# CAN_v1.net
KiCad netlist of a schematic drawn in Altium Designer
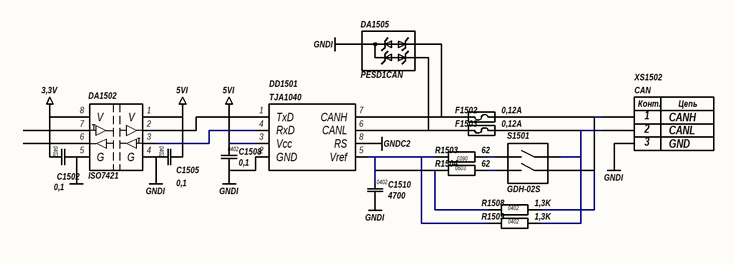
[diagram p0: CAN v1.SchDoc]

(export (version "E")
  (design (tool "Eeschema 10.0.6"))
  (components
    (comp (ref "C1502")
      (value "0,1")
      (footprint "CAP0402")
      (description "Конденсатор чип")
      (libsource (lib "EwgPassive") (part "CAP_0402"))
    )
    (comp (ref "C1505")
      (value "0,1")
      (footprint "CAP0402")
      (description "Конденсатор чип")
      (libsource (lib "EwgPassive") (part "CAP_0402"))
    )
    (comp (ref "C1508")
      (value "0,1")
      (footprint "CAP0402")
      (description "Конденсатор чип")
      (libsource (lib "EwgPassive") (part "CAP_0402"))
    )
    (comp (ref "C1510")
      (value "4700")
      (footprint "CAP0402")
      (description "Конденсатор чип")
      (libsource (lib "EwgPassive") (part "CAP_0402"))
    )
    (comp (ref "DA1502")
      (value "ISO7421")
      (footprint "SO8")
      (description "Цифровой изолятор 1 вх 1 вых")
      (libsource (lib "EwgOpto") (part "ISO7421"))
    )
    (comp (ref "DA1505")
      (value "PESD1CAN")
      (footprint "SOT-23")
      (description "ESD-CAN защита")
      (libsource (lib "EwgActive") (part "PESD1CAN"))
    )
    (comp (ref "DD1501")
      (value "TJA1040")
      (footprint "SO8")
      (description "Драйвер CAN")
      (libsource (lib "EwgMicrochips") (part "TJA1040"))
    )
    (comp (ref "F1502")
      (value "0,12A")
      (footprint "MF-NSMF")
      (description "Предохранитель самовосстанавливающийся")
      (libsource (lib "EwgPassive") (part "MF-NSMF"))
    )
    (comp (ref "F1503")
      (value "0,12A")
      (footprint "MF-NSMF")
      (description "Предохранитель самовосстанавливающийся")
      (libsource (lib "EwgPassive") (part "MF-NSMF"))
    )
    (comp (ref "R1503")
      (value "62")
      (footprint "RES0603")
      (description "Резистор чип")
      (libsource (lib "") (part "RES_0603_1"))
    )
    (comp (ref "R1504")
      (value "62")
      (footprint "RES0603")
      (description "Резистор чип")
      (libsource (lib "EwgPassive") (part "RES_0603"))
    )
    (comp (ref "R1508")
      (value "1,3K")
      (footprint "RES0402")
      (description "Резистор чип")
      (libsource (lib "EwgPassive") (part "RES_0402"))
    )
    (comp (ref "R1509")
      (value "1,3K")
      (footprint "RES0402")
      (description "Резистор чип")
      (libsource (lib "EwgPassive") (part "RES_0402"))
    )
    (comp (ref "S1501")
      (value "GDH-02S")
      (footprint "GDH02S")
      (description "DIP-переключатель")
      (libsource (lib "EwgSwitchers") (part "GDH02S"))
    )
    (comp (ref "XS1502")
      (value "CAN")
      (footprint "MW-3M")
      (description "Разъем")
      (libsource (lib "EwgConnectors") (part "Разъем3_1"))
    )
  )
  (nets
    (net (code "1") (name "3,3V") (class "Default")
      (node (ref "C1502") (pin "1") (pintype "passive"))
      (node (ref "DA1502") (pin "8") (pinfunction "V_8") (pintype "passive"))
    )
    (net (code "2") (name "5VI") (class "Default")
      (node (ref "C1505") (pin "2") (pintype "passive"))
      (node (ref "C1508") (pin "1") (pintype "passive"))
      (node (ref "DA1502") (pin "1") (pinfunction "V_1") (pintype "passive"))
      (node (ref "DD1501") (pin "3") (pinfunction "Vcc_3") (pintype "passive"))
    )
    (net (code "3") (name "GND") (class "Default")
      (node (ref "C1502") (pin "2") (pintype "passive"))
      (node (ref "DA1502") (pin "5") (pinfunction "G_5") (pintype "passive"))
    )
    (net (code "4") (name "GNDC2") (class "Default")
      (node (ref "DD1501") (pin "8") (pinfunction "RS_8") (pintype "passive"))
    )
    (net (code "5") (name "GNDI") (class "Default")
      (node (ref "C1505") (pin "1") (pintype "passive"))
      (node (ref "C1508") (pin "2") (pintype "passive"))
      (node (ref "C1510") (pin "2") (pintype "passive"))
      (node (ref "DA1502") (pin "4") (pinfunction "G_4") (pintype "passive"))
      (node (ref "DA1505") (pin "3") (pinfunction "K3_3") (pintype "passive"))
      (node (ref "DD1501") (pin "2") (pinfunction "GND_2") (pintype "passive"))
      (node (ref "XS1502") (pin "3") (pinfunction "GND_3") (pintype "passive"))
    )
    (net (code "6") (name "Net-(DA1505-K1)") (class "Default")
      (node (ref "DA1505") (pin "1") (pinfunction "K1_1") (pintype "passive"))
      (node (ref "DD1501") (pin "7") (pinfunction "CANH_7") (pintype "passive"))
      (node (ref "F1502") (pin "1") (pintype "passive"))
    )
    (net (code "7") (name "Net-(DA1505-K2)") (class "Default")
      (node (ref "DA1505") (pin "2") (pinfunction "K2_2") (pintype "passive"))
      (node (ref "DD1501") (pin "6") (pinfunction "CANL_6") (pintype "passive"))
      (node (ref "F1503") (pin "1") (pintype "passive"))
    )
    (net (code "8") (name "Net-(DD1501-RxD)") (class "Default")
      (node (ref "DA1502") (pin "3") (pintype "passive"))
      (node (ref "DD1501") (pin "4") (pinfunction "RxD_4") (pintype "passive"))
    )
    (net (code "9") (name "Net-(DD1501-TxD)") (class "Default")
      (node (ref "DA1502") (pin "2") (pintype "passive"))
      (node (ref "DD1501") (pin "1") (pinfunction "TxD_1") (pintype "passive"))
    )
    (net (code "10") (name "Net-(DD1501-Vref)") (class "Default")
      (node (ref "C1510") (pin "1") (pintype "passive"))
      (node (ref "DD1501") (pin "5") (pinfunction "Vref_5") (pintype "passive"))
      (node (ref "R1503") (pin "2") (pintype "passive"))
      (node (ref "R1504") (pin "1") (pintype "passive"))
      (node (ref "R1508") (pin "1") (pintype "passive"))
      (node (ref "R1509") (pin "1") (pintype "passive"))
    )
    (net (code "11") (name "Net-(S1501-1-4)") (class "Default")
      (node (ref "F1503") (pin "2") (pintype "passive"))
      (node (ref "R1509") (pin "2") (pintype "passive"))
      (node (ref "S1501") (pin "1") (pinfunction "1-4_1") (pintype "passive"))
      (node (ref "XS1502") (pin "2") (pinfunction "CANL_2") (pintype "passive"))
    )
    (net (code "12") (name "Net-(S1501-2-3)") (class "Default")
      (node (ref "F1502") (pin "2") (pintype "passive"))
      (node (ref "R1508") (pin "2") (pintype "passive"))
      (node (ref "S1501") (pin "2") (pinfunction "2-3_2") (pintype "passive"))
      (node (ref "XS1502") (pin "1") (pinfunction "CANH_1") (pintype "passive"))
    )
    (net (code "13") (name "Net-(S1501-3-2)") (class "Default")
      (node (ref "R1504") (pin "2") (pintype "passive"))
      (node (ref "S1501") (pin "3") (pinfunction "3-2_3") (pintype "passive"))
    )
    (net (code "14") (name "Net-(S1501-4-1)") (class "Default")
      (node (ref "R1503") (pin "1") (pintype "passive"))
      (node (ref "S1501") (pin "4") (pinfunction "4-1_4") (pintype "passive"))
    )
    (net (code "15") (name "unconnected-(DA1502-Pad6)") (class "Default")
      (node (ref "DA1502") (pin "6") (pintype "passive"))
    )
    (net (code "16") (name "unconnected-(DA1502-Pad7)") (class "Default")
      (node (ref "DA1502") (pin "7") (pintype "passive"))
    )
  )
)
